# trigger.net
KiCad netlist of a schematic drawn in EAGLE
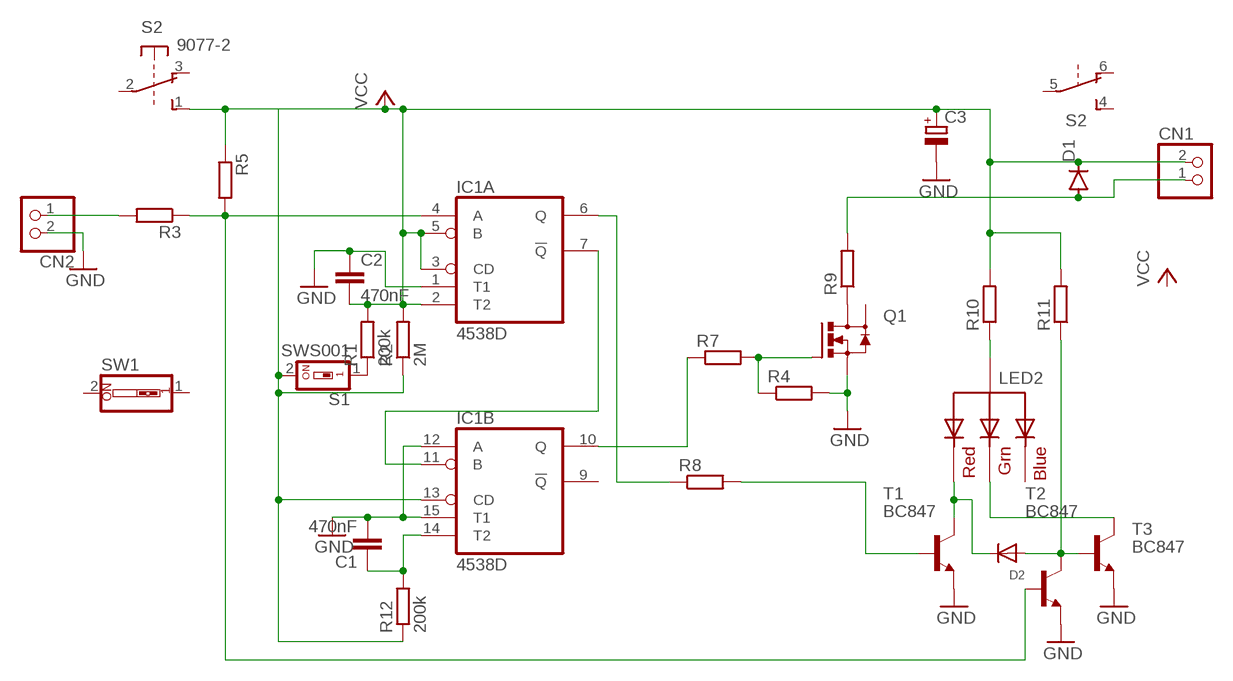
[diagram p0: schematic, sheet 1]

(export (version "E")
  (design (tool "Eeschema 10.0.6"))
  (components
    (comp (ref "C1")
      (value "470nF")
      (footprint "eagle-import:C0805")
      (libsource (lib "eagle-import") (part "C"))
    )
    (comp (ref "C2")
      (value "470nF")
      (footprint "eagle-import:C0805")
      (libsource (lib "eagle-import") (part "C"))
    )
    (comp (ref "C3")
      (value "CPOL-EUE5-13")
      (footprint "eagle-import:E5-13")
      (libsource (lib "eagle-import") (part "CPOL-EUE5-13"))
    )
    (comp (ref "CN1")
      (value "JST_2PIN-THM")
      (footprint "eagle-import:JST-PH-2-THM")
      (libsource (lib "eagle-import") (part "JST_2PIN-THM"))
    )
    (comp (ref "CN2")
      (value "JST_2PIN-THM")
      (footprint "eagle-import:JST-PH-2-THM")
      (libsource (lib "eagle-import") (part "JST_2PIN-THM"))
    )
    (comp (ref "D1")
      (value "DIODE-DO214AC")
      (footprint "eagle-import:DO214AC")
      (libsource (lib "eagle-import") (part "DIODE-DO214AC"))
    )
    (comp (ref "D2")
      (value "DIODESMA")
      (footprint "eagle-import:SMADIODE")
      (libsource (lib "eagle-import") (part "DIODESMA"))
    )
    (comp (ref "IC1")
      (value "4538D")
      (footprint "eagle-import:SO16")
      (libsource (lib "eagle-import") (part "4538D"))
    )
    (comp (ref "LED2")
      (value "RGBLED_CA-5MM")
      (footprint "eagle-import:LED5MMRGB")
      (libsource (lib "eagle-import") (part "RGBLED_CA-5MM"))
    )
    (comp (ref "Q1")
      (value "MOSFET_N_SOT223")
      (footprint "eagle-import:SOT223")
      (libsource (lib "eagle-import") (part "MOSFET_N_SOT223"))
    )
    (comp (ref "R1")
      (value "200k")
      (footprint "eagle-import:R1206")
      (libsource (lib "eagle-import") (part "RR1206"))
    )
    (comp (ref "R2")
      (value "2M")
      (footprint "eagle-import:R1206")
      (libsource (lib "eagle-import") (part "RR1206"))
    )
    (comp (ref "R3")
      (value "RR1206")
      (footprint "eagle-import:R1206")
      (libsource (lib "eagle-import") (part "RR1206"))
    )
    (comp (ref "R4")
      (value "RR1206")
      (footprint "eagle-import:R1206")
      (libsource (lib "eagle-import") (part "RR1206"))
    )
    (comp (ref "R5")
      (value "RR1206")
      (footprint "eagle-import:R1206")
      (libsource (lib "eagle-import") (part "RR1206"))
    )
    (comp (ref "R7")
      (value "RR1206")
      (footprint "eagle-import:R1206")
      (libsource (lib "eagle-import") (part "RR1206"))
    )
    (comp (ref "R8")
      (value "RR1206")
      (footprint "eagle-import:R1206")
      (libsource (lib "eagle-import") (part "RR1206"))
    )
    (comp (ref "R9")
      (value "RR1206")
      (footprint "eagle-import:R1206")
      (libsource (lib "eagle-import") (part "RR1206"))
    )
    (comp (ref "R10")
      (value "R")
      (footprint "eagle-import:R0805")
      (libsource (lib "eagle-import") (part "R"))
    )
    (comp (ref "R11")
      (value "R")
      (footprint "eagle-import:R0805")
      (libsource (lib "eagle-import") (part "R"))
    )
    (comp (ref "R12")
      (value "200k")
      (footprint "eagle-import:R1206")
      (libsource (lib "eagle-import") (part "RR1206"))
    )
    (comp (ref "S1")
      (value "SWS001")
      (footprint "eagle-import:SMS-001")
      (libsource (lib "eagle-import") (part "SWS001"))
    )
    (comp (ref "S2")
      (value "9077-2")
      (footprint "eagle-import:9077-2")
      (libsource (lib "eagle-import") (part "9077-2"))
    )
    (comp (ref "SW1")
      (value "SW_DIP-1")
      (footprint "eagle-import:EDG-01")
      (libsource (lib "eagle-import") (part "SW_DIP-1"))
    )
    (comp (ref "T1")
      (value "BC847")
      (footprint "eagle-import:SOT23")
      (libsource (lib "eagle-import") (part "BC847"))
    )
    (comp (ref "T2")
      (value "BC847")
      (footprint "eagle-import:SOT23")
      (libsource (lib "eagle-import") (part "BC847"))
    )
    (comp (ref "T3")
      (value "BC847")
      (footprint "eagle-import:SOT23")
      (libsource (lib "eagle-import") (part "transistor_402_BC847"))
    )
  )
  (nets
    (net (code "1") (name "GND") (class "Default")
      (node (ref "C1") (pin "2") (pinfunction "2_2") (pintype "passive"))
      (node (ref "C2") (pin "1") (pinfunction "1_1") (pintype "passive"))
      (node (ref "C3") (pin "-") (pinfunction "-_-") (pintype "passive"))
      (node (ref "CN2") (pin "2") (pinfunction "1_2") (pintype "passive"))
      (node (ref "IC1") (pin "1") (pinfunction "T1_1") (pintype "input"))
      (node (ref "IC1") (pin "12") (pinfunction "A_12") (pintype "input"))
      (node (ref "IC1") (pin "15") (pinfunction "T1_15") (pintype "input"))
      (node (ref "Q1") (pin "3") (pinfunction "S_3") (pintype "passive"))
      (node (ref "R4") (pin "2") (pinfunction "2_2") (pintype "passive"))
      (node (ref "T1") (pin "2") (pinfunction "E_2") (pintype "passive"))
      (node (ref "T2") (pin "2") (pinfunction "E_2") (pintype "passive"))
      (node (ref "T3") (pin "2") (pinfunction "E_2") (pintype "passive"))
    )
    (net (code "2") (name "Net-(CN1-2)") (class "Default")
      (node (ref "CN1") (pin "1") (pinfunction "2_1") (pintype "passive"))
      (node (ref "D1") (pin "A") (pinfunction "A_A") (pintype "passive"))
      (node (ref "R9") (pin "2") (pinfunction "2_2") (pintype "passive"))
    )
    (net (code "3") (name "Net-(CN2-2)") (class "Default")
      (node (ref "CN2") (pin "1") (pinfunction "2_1") (pintype "passive"))
      (node (ref "R3") (pin "2") (pinfunction "2_2") (pintype "passive"))
    )
    (net (code "4") (name "Net-(IC1A-A)") (class "Default")
      (node (ref "IC1") (pin "4") (pinfunction "A_4") (pintype "input"))
      (node (ref "R3") (pin "1") (pinfunction "1_1") (pintype "passive"))
      (node (ref "R5") (pin "2") (pinfunction "2_2") (pintype "passive"))
      (node (ref "T3") (pin "1") (pinfunction "B_1") (pintype "passive"))
    )
    (net (code "5") (name "Net-(IC1A-Q)") (class "Default")
      (node (ref "IC1") (pin "6") (pinfunction "Q_6") (pintype "output"))
      (node (ref "R8") (pin "1") (pinfunction "1_1") (pintype "passive"))
    )
    (net (code "6") (name "Net-(IC1A-~{Q})") (class "Default")
      (node (ref "IC1") (pin "11") (pinfunction "B_11") (pintype "input"))
      (node (ref "IC1") (pin "7") (pinfunction "~{Q}_7") (pintype "output"))
    )
    (net (code "7") (name "Net-(IC1B-Q)") (class "Default")
      (node (ref "IC1") (pin "10") (pinfunction "Q_10") (pintype "output"))
      (node (ref "R7") (pin "1") (pinfunction "1_1") (pintype "passive"))
    )
    (net (code "8") (name "Net-(IC1B-T2)") (class "Default")
      (node (ref "C1") (pin "1") (pinfunction "1_1") (pintype "passive"))
      (node (ref "IC1") (pin "14") (pinfunction "T2_14") (pintype "input"))
      (node (ref "R12") (pin "2") (pinfunction "2_2") (pintype "passive"))
    )
    (net (code "9") (name "Net-(LED2-GREEN)") (class "Default")
      (node (ref "LED2") (pin "3") (pinfunction "GREEN_3") (pintype "bidirectional"))
      (node (ref "T2") (pin "3") (pinfunction "C_3") (pintype "passive"))
    )
    (net (code "10") (name "Net-(LED2-RED)") (class "Default")
      (node (ref "D2") (pin "C") (pinfunction "C_C") (pintype "passive"))
      (node (ref "LED2") (pin "1") (pinfunction "RED_1") (pintype "bidirectional"))
      (node (ref "T1") (pin "3") (pinfunction "C_3") (pintype "passive"))
    )
    (net (code "11") (name "Net-(LED2-VCC)") (class "Default")
      (node (ref "LED2") (pin "2") (pinfunction "VCC_2") (pintype "bidirectional"))
      (node (ref "R10") (pin "1") (pinfunction "1_1") (pintype "passive"))
    )
    (net (code "12") (name "Net-(Q1-D)") (class "Default")
      (node (ref "Q1") (pin "2") (pinfunction "D_2") (pintype "passive"))
      (node (ref "R9") (pin "1") (pinfunction "1_1") (pintype "passive"))
    )
    (net (code "13") (name "Net-(Q1-G)") (class "Default")
      (node (ref "Q1") (pin "1") (pinfunction "G_1") (pintype "passive"))
      (node (ref "R4") (pin "1") (pinfunction "1_1") (pintype "passive"))
      (node (ref "R7") (pin "2") (pinfunction "2_2") (pintype "passive"))
    )
    (net (code "14") (name "Net-(R1-Pad1)") (class "Default")
      (node (ref "R1") (pin "1") (pinfunction "1_1") (pintype "passive"))
      (node (ref "S1") (pin "1") (pinfunction "1_1") (pintype "passive"))
    )
    (net (code "15") (name "Net-(T1-B)") (class "Default")
      (node (ref "R8") (pin "2") (pinfunction "2_2") (pintype "passive"))
      (node (ref "T1") (pin "1") (pinfunction "B_1") (pintype "passive"))
    )
    (net (code "16") (name "Net-(T2-B)") (class "Default")
      (node (ref "D2") (pin "A") (pinfunction "A_A") (pintype "passive"))
      (node (ref "R11") (pin "1") (pinfunction "1_1") (pintype "passive"))
      (node (ref "T2") (pin "1") (pinfunction "B_1") (pintype "passive"))
      (node (ref "T3") (pin "3") (pinfunction "C_3") (pintype "passive"))
    )
    (net (code "17") (name "VCC") (class "Default")
      (node (ref "C2") (pin "2") (pinfunction "2_2") (pintype "passive"))
      (node (ref "C3") (pin "+") (pinfunction "+_+") (pintype "passive"))
      (node (ref "CN1") (pin "2") (pinfunction "1_2") (pintype "passive"))
      (node (ref "D1") (pin "C") (pinfunction "C_C") (pintype "passive"))
      (node (ref "IC1") (pin "13") (pinfunction "CD_13") (pintype "input"))
      (node (ref "IC1") (pin "2") (pinfunction "T2_2") (pintype "input"))
      (node (ref "IC1") (pin "3") (pinfunction "CD_3") (pintype "input"))
      (node (ref "IC1") (pin "5") (pinfunction "B_5") (pintype "input"))
      (node (ref "R1") (pin "2") (pinfunction "2_2") (pintype "passive"))
      (node (ref "R10") (pin "2") (pinfunction "2_2") (pintype "passive"))
      (node (ref "R11") (pin "2") (pinfunction "2_2") (pintype "passive"))
      (node (ref "R12") (pin "1") (pinfunction "1_1") (pintype "passive"))
      (node (ref "R2") (pin "1") (pinfunction "1_1") (pintype "passive"))
      (node (ref "R2") (pin "2") (pinfunction "2_2") (pintype "passive"))
      (node (ref "R5") (pin "1") (pinfunction "1_1") (pintype "passive"))
      (node (ref "S1") (pin "2") (pinfunction "2_2") (pintype "passive"))
      (node (ref "S2") (pin "1") (pinfunction "S_1") (pintype "passive"))
    )
    (net (code "18") (name "unconnected-(IC1B-~{Q}-Pad9)") (class "Default")
      (node (ref "IC1") (pin "9") (pinfunction "~{Q}_9") (pintype "output"))
    )
    (net (code "19") (name "unconnected-(LED2-BLUE-Pad4)") (class "Default")
      (node (ref "LED2") (pin "4") (pinfunction "BLUE_4") (pintype "bidirectional"))
    )
    (net (code "20") (name "unconnected-(Q1-D1-Pad4)") (class "Default")
      (node (ref "Q1") (pin "4") (pinfunction "D1_4") (pintype "passive"))
    )
    (net (code "21") (name "unconnected-(S2A-O-Pad3)") (class "Default")
      (node (ref "S2") (pin "3") (pinfunction "O_3") (pintype "passive"))
    )
    (net (code "22") (name "unconnected-(S2A-P-Pad2)") (class "Default")
      (node (ref "S2") (pin "2") (pinfunction "P_2") (pintype "passive"))
    )
    (net (code "23") (name "unconnected-(S2B-O-Pad6)") (class "Default")
      (node (ref "S2") (pin "6") (pinfunction "O_6") (pintype "passive"))
    )
    (net (code "24") (name "unconnected-(S2B-P-Pad5)") (class "Default")
      (node (ref "S2") (pin "5") (pinfunction "P_5") (pintype "passive"))
    )
    (net (code "25") (name "unconnected-(S2B-S-Pad4)") (class "Default")
      (node (ref "S2") (pin "4") (pinfunction "S_4") (pintype "passive"))
    )
    (net (code "26") (name "unconnected-(SW1-Pad1)") (class "Default")
      (node (ref "SW1") (pin "1") (pinfunction "1_1") (pintype "passive"))
    )
    (net (code "27") (name "unconnected-(SW1-Pad2)") (class "Default")
      (node (ref "SW1") (pin "2") (pinfunction "2_2") (pintype "passive"))
    )
  )
)
